# UPU.net
KiCad netlist of a schematic drawn in EAGLE
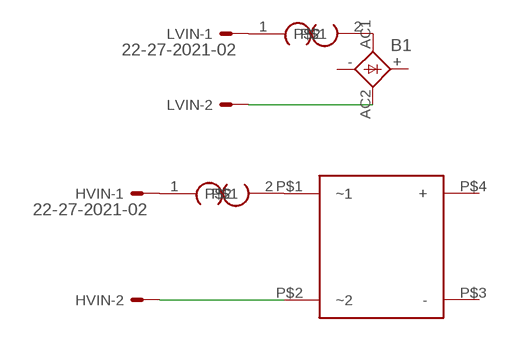
[diagram p0: schematic, sheet 1]

(export (version "E")
  (design (tool "Eeschema 10.0.6"))
  (components
    (comp (ref "B1")
      (value "GBPC6")
      (footprint "eagle-import:GBPC6")
      (libsource (lib "eagle-import") (part "GBPC6"))
    )
    (comp (ref "HVIN")
      (value "22-27-2021-02")
      (footprint "eagle-import:6410-02")
      (libsource (lib "eagle-import") (part "22-?-0227-2021"))
    )
    (comp (ref "LVIN")
      (value "22-27-2021-02")
      (footprint "eagle-import:6410-02")
      (libsource (lib "eagle-import") (part "22-?-0227-2021"))
    )
    (comp (ref "U$1")
      (value "KWS25A")
      (footprint "eagle-import:KWS")
      (libsource (lib "eagle-import") (part "KWS25A"))
    )
    (comp (ref "U$2")
      (value "MMUFUSE")
      (footprint "eagle-import:0204V")
      (libsource (lib "eagle-import") (part "MMUFUSE"))
    )
    (comp (ref "U$3")
      (value "MMUFUSE")
      (footprint "eagle-import:0204V")
      (libsource (lib "eagle-import") (part "MMUFUSE"))
    )
  )
  (nets
    (net (code "1") (name "Net-(HVINA-S)") (class "Default")
      (node (ref "HVIN") (pin "1") (pinfunction "S_1") (pintype "passive"))
      (node (ref "U$3") (pin "1") (pinfunction "P$1_1") (pintype "bidirectional"))
    )
    (net (code "2") (name "Net-(HVINB-S)") (class "Default")
      (node (ref "HVIN") (pin "2") (pinfunction "S_2") (pintype "passive"))
      (node (ref "U$1") (pin "P$2") (pinfunction "~{2}_P$2") (pintype "bidirectional"))
    )
    (net (code "3") (name "Net-(LVINA-S)") (class "Default")
      (node (ref "LVIN") (pin "1") (pinfunction "S_1") (pintype "passive"))
      (node (ref "U$2") (pin "1") (pinfunction "P$1_1") (pintype "bidirectional"))
    )
    (net (code "4") (name "Net-(LVINB-S)") (class "Default")
      (node (ref "B1") (pin "AC2") (pinfunction "AC2_AC2") (pintype "passive"))
      (node (ref "LVIN") (pin "2") (pinfunction "S_2") (pintype "passive"))
    )
    (net (code "5") (name "Net-(U$1-~{1})") (class "Default")
      (node (ref "U$1") (pin "P$1") (pinfunction "~{1}_P$1") (pintype "bidirectional"))
      (node (ref "U$3") (pin "2") (pinfunction "P$2_2") (pintype "bidirectional"))
    )
    (net (code "6") (name "Net-(U$2-P$2)") (class "Default")
      (node (ref "B1") (pin "AC1") (pinfunction "AC1_AC1") (pintype "passive"))
      (node (ref "U$2") (pin "2") (pinfunction "P$2_2") (pintype "bidirectional"))
    )
    (net (code "7") (name "unconnected-(B1-Pad+)") (class "Default")
      (node (ref "B1") (pin "+") (pinfunction "+_+") (pintype "passive"))
    )
    (net (code "8") (name "unconnected-(B1-Pad-)") (class "Default")
      (node (ref "B1") (pin "-") (pinfunction "-_-") (pintype "passive"))
    )
    (net (code "9") (name "unconnected-(U$1-+-PadP$4)") (class "Default")
      (node (ref "U$1") (pin "P$4") (pinfunction "+_P$4") (pintype "bidirectional"))
    )
    (net (code "10") (name "unconnected-(U$1---PadP$3)") (class "Default")
      (node (ref "U$1") (pin "P$3") (pinfunction "-_P$3") (pintype "bidirectional"))
    )
  )
)
